# Template.net
KiCad netlist of a schematic drawn in EAGLE
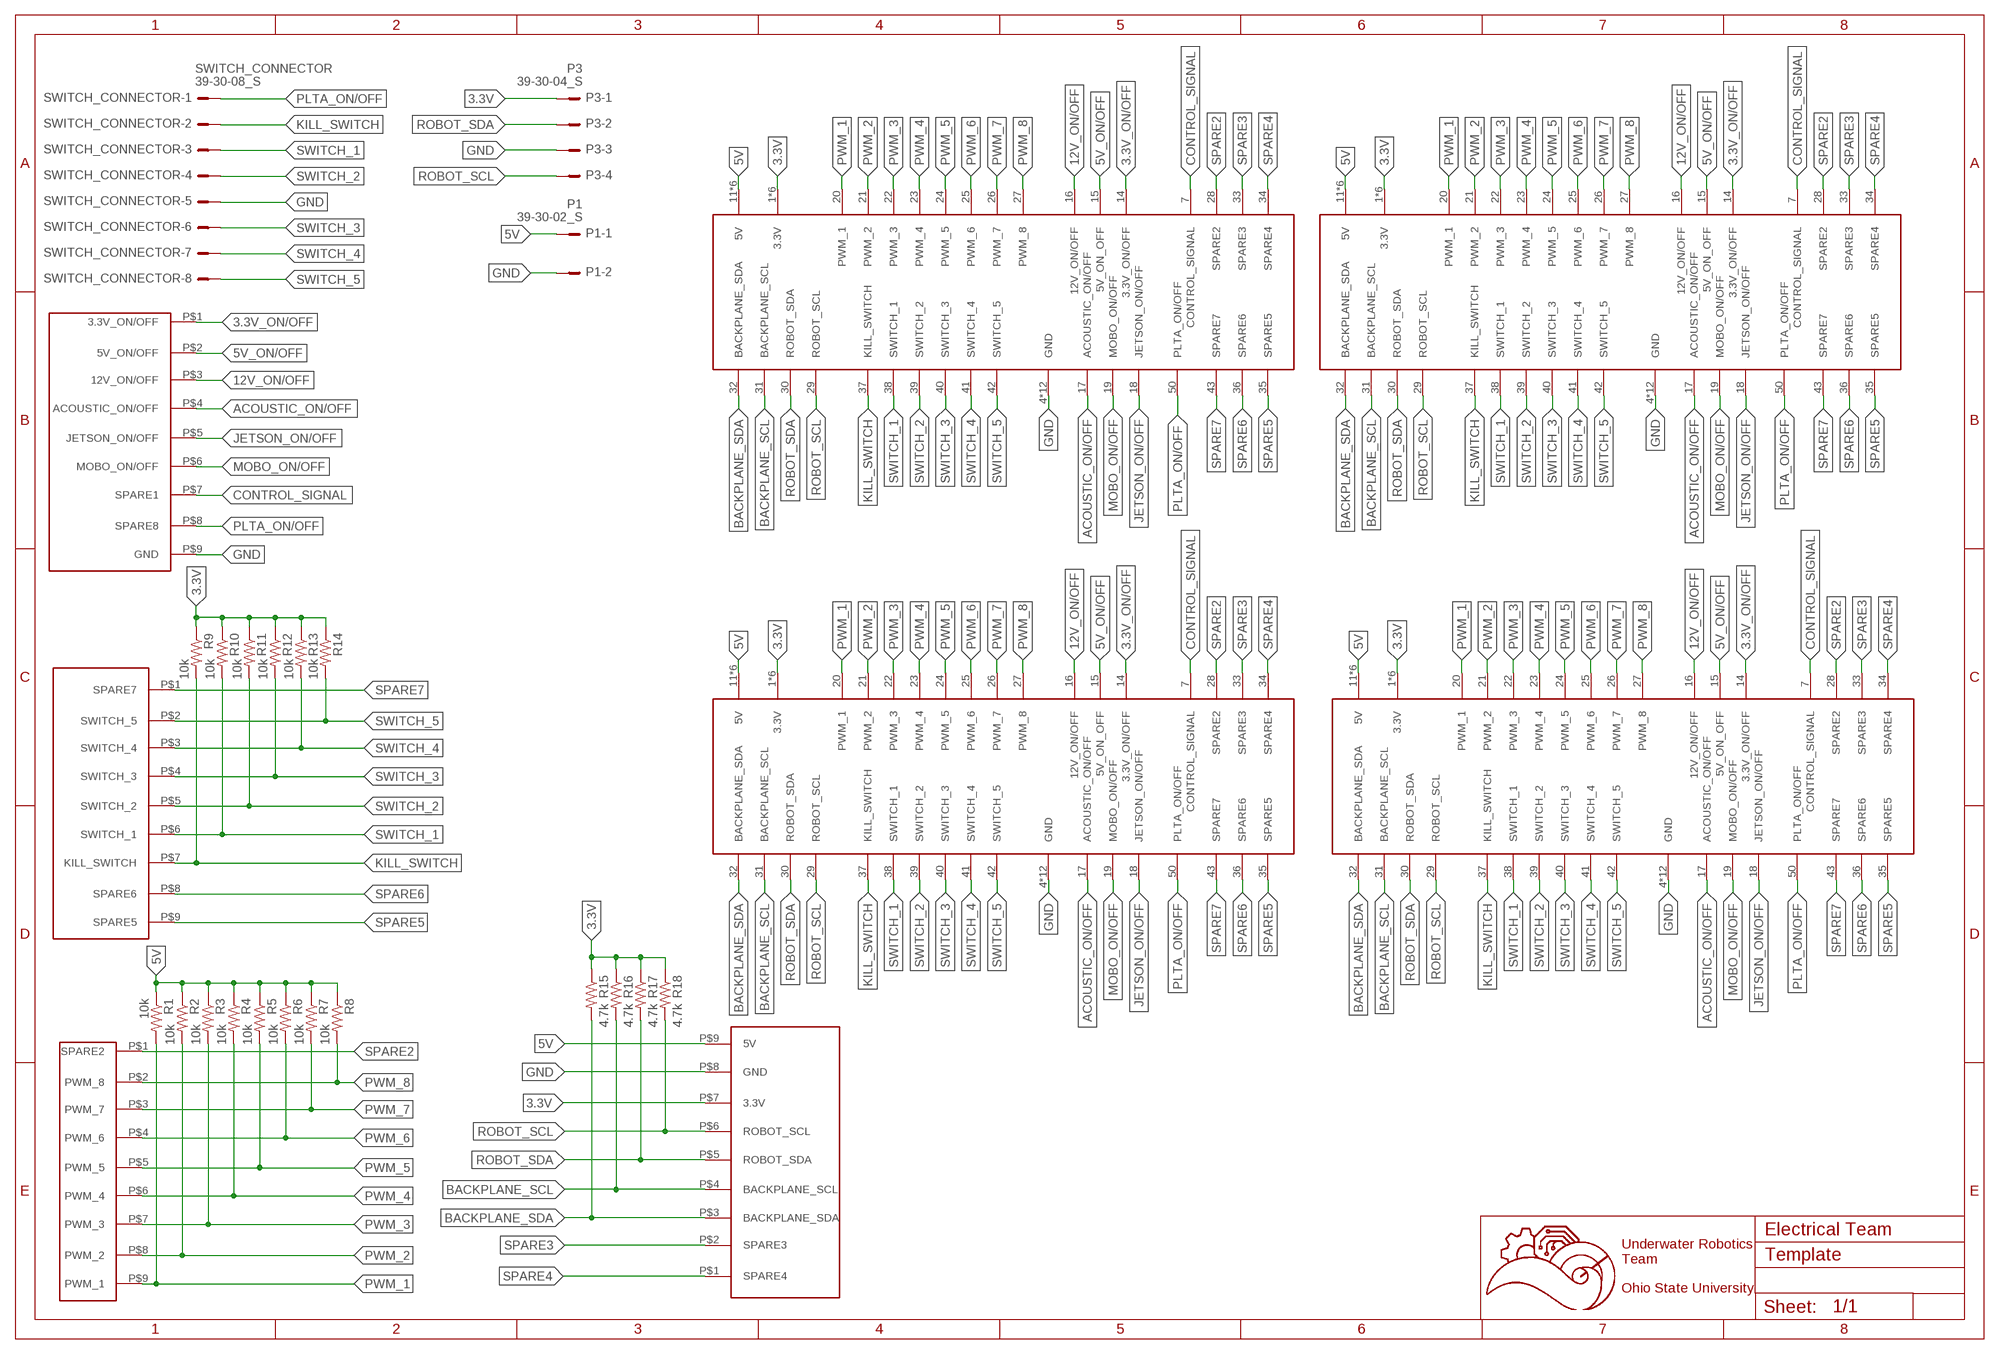
[diagram p0: schematic, sheet 1]

(export (version "E")
  (design (tool "Eeschema 10.0.6"))
  (components
    (comp (ref "P1")
      (value "39-30-02_S")
      (footprint "eagle-import:39-30-_02_")
      (libsource (lib "eagle-import") (part "39-30-?02?_S"))
    )
    (comp (ref "P3")
      (value "39-30-04_S")
      (footprint "eagle-import:39-30-_04_")
      (libsource (lib "eagle-import") (part "39-30-?04?_S"))
    )
    (comp (ref "R1")
      (value "10k")
      (footprint "eagle-import:R0603")
      (libsource (lib "eagle-import") (part "R-US_R0603"))
    )
    (comp (ref "R2")
      (value "10k")
      (footprint "eagle-import:R0603")
      (libsource (lib "eagle-import") (part "R-US_R0603"))
    )
    (comp (ref "R3")
      (value "10k")
      (footprint "eagle-import:R0603")
      (libsource (lib "eagle-import") (part "R-US_R0603"))
    )
    (comp (ref "R4")
      (value "10k")
      (footprint "eagle-import:R0603")
      (libsource (lib "eagle-import") (part "R-US_R0603"))
    )
    (comp (ref "R5")
      (value "10k")
      (footprint "eagle-import:R0603")
      (libsource (lib "eagle-import") (part "R-US_R0603"))
    )
    (comp (ref "R6")
      (value "10k")
      (footprint "eagle-import:R0603")
      (libsource (lib "eagle-import") (part "R-US_R0603"))
    )
    (comp (ref "R7")
      (value "10k")
      (footprint "eagle-import:R0603")
      (libsource (lib "eagle-import") (part "R-US_R0603"))
    )
    (comp (ref "R8")
      (value "10k")
      (footprint "eagle-import:R0603")
      (libsource (lib "eagle-import") (part "R-US_R0603"))
    )
    (comp (ref "R9")
      (value "10k")
      (footprint "eagle-import:R0603")
      (libsource (lib "eagle-import") (part "R-US_R0603"))
    )
    (comp (ref "R10")
      (value "10k")
      (footprint "eagle-import:R0603")
      (libsource (lib "eagle-import") (part "R-US_R0603"))
    )
    (comp (ref "R11")
      (value "10k")
      (footprint "eagle-import:R0603")
      (libsource (lib "eagle-import") (part "R-US_R0603"))
    )
    (comp (ref "R12")
      (value "10k")
      (footprint "eagle-import:R0603")
      (libsource (lib "eagle-import") (part "R-US_R0603"))
    )
    (comp (ref "R13")
      (value "10k")
      (footprint "eagle-import:R0603")
      (libsource (lib "eagle-import") (part "R-US_R0603"))
    )
    (comp (ref "R14")
      (value "10k")
      (footprint "eagle-import:R0603")
      (libsource (lib "eagle-import") (part "R-US_R0603"))
    )
    (comp (ref "R15")
      (value "4.7k")
      (footprint "eagle-import:R0603")
      (libsource (lib "eagle-import") (part "R-US_R0603"))
    )
    (comp (ref "R16")
      (value "4.7k")
      (footprint "eagle-import:R0603")
      (libsource (lib "eagle-import") (part "R-US_R0603"))
    )
    (comp (ref "R17")
      (value "4.7k")
      (footprint "eagle-import:R0603")
      (libsource (lib "eagle-import") (part "R-US_R0603"))
    )
    (comp (ref "R18")
      (value "4.7k")
      (footprint "eagle-import:R0603")
      (libsource (lib "eagle-import") (part "R-US_R0603"))
    )
    (comp (ref "SWITCH_CONNECTOR")
      (value "39-30-08_S")
      (footprint "eagle-import:39-30-_08_")
      (libsource (lib "eagle-import") (part "39-30-?08?_S"))
    )
    (comp (ref "U$1")
      (value "5530843-FEMALE")
      (footprint "eagle-import:5530843-6-BACKPLANEMATE")
      (libsource (lib "eagle-import") (part "5530843-FEMALE"))
    )
    (comp (ref "U$2")
      (value "5530843-FEMALE")
      (footprint "eagle-import:5530843-6-BACKPLANEMATE")
      (libsource (lib "eagle-import") (part "5530843-FEMALE"))
    )
    (comp (ref "U$3")
      (value "5530843-FEMALE")
      (footprint "eagle-import:5530843-6-BACKPLANEMATE")
      (libsource (lib "eagle-import") (part "5530843-FEMALE"))
    )
    (comp (ref "U$4")
      (value "5530843-FEMALE")
      (footprint "eagle-import:5530843-6-BACKPLANEMATE")
      (libsource (lib "eagle-import") (part "5530843-FEMALE"))
    )
    (comp (ref "U$5")
      (value "929870-01-09_1")
      (footprint "eagle-import:929852-01-09_1ROW")
      (libsource (lib "eagle-import") (part "929870-01-09_1"))
    )
    (comp (ref "U$6")
      (value "929870-01-09_2")
      (footprint "eagle-import:929852-01-09_1ROW")
      (libsource (lib "eagle-import") (part "929870-01-09_2"))
    )
    (comp (ref "U$7")
      (value "929870-01-09_3")
      (footprint "eagle-import:929852-01-09_1ROW")
      (libsource (lib "eagle-import") (part "929870-01-09_3"))
    )
    (comp (ref "U$8")
      (value "929870-01-09_4")
      (footprint "eagle-import:929852-01-09_1ROW")
      (libsource (lib "eagle-import") (part "929870-01-09_4"))
    )
  )
  (nets
    (net (code "1") (name "3.3V") (class "Default")
      (node (ref "P3") (pin "1") (pinfunction "P_1") (pintype "passive"))
      (node (ref "R10") (pin "1") (pinfunction "1_1") (pintype "passive"))
      (node (ref "R11") (pin "1") (pinfunction "1_1") (pintype "passive"))
      (node (ref "R12") (pin "1") (pinfunction "1_1") (pintype "passive"))
      (node (ref "R13") (pin "1") (pinfunction "1_1") (pintype "passive"))
      (node (ref "R14") (pin "1") (pinfunction "1_1") (pintype "passive"))
      (node (ref "R15") (pin "1") (pinfunction "1_1") (pintype "passive"))
      (node (ref "R16") (pin "1") (pinfunction "1_1") (pintype "passive"))
      (node (ref "R17") (pin "1") (pinfunction "1_1") (pintype "passive"))
      (node (ref "R18") (pin "1") (pinfunction "1_1") (pintype "passive"))
      (node (ref "R9") (pin "1") (pinfunction "1_1") (pintype "passive"))
      (node (ref "U$1") (pin "1") (pinfunction "3.3V_1") (pintype "bidirectional"))
      (node (ref "U$1") (pin "2") (pinfunction "3.3V_2") (pintype "bidirectional"))
      (node (ref "U$1") (pin "3") (pinfunction "3.3V_3") (pintype "bidirectional"))
      (node (ref "U$1") (pin "54") (pinfunction "3.3V_54") (pintype "bidirectional"))
      (node (ref "U$1") (pin "55") (pinfunction "3.3V_55") (pintype "bidirectional"))
      (node (ref "U$1") (pin "56") (pinfunction "3.3V_56") (pintype "bidirectional"))
      (node (ref "U$2") (pin "1") (pinfunction "3.3V_1") (pintype "bidirectional"))
      (node (ref "U$2") (pin "2") (pinfunction "3.3V_2") (pintype "bidirectional"))
      (node (ref "U$2") (pin "3") (pinfunction "3.3V_3") (pintype "bidirectional"))
      (node (ref "U$2") (pin "54") (pinfunction "3.3V_54") (pintype "bidirectional"))
      (node (ref "U$2") (pin "55") (pinfunction "3.3V_55") (pintype "bidirectional"))
      (node (ref "U$2") (pin "56") (pinfunction "3.3V_56") (pintype "bidirectional"))
      (node (ref "U$3") (pin "1") (pinfunction "3.3V_1") (pintype "bidirectional"))
      (node (ref "U$3") (pin "2") (pinfunction "3.3V_2") (pintype "bidirectional"))
      (node (ref "U$3") (pin "3") (pinfunction "3.3V_3") (pintype "bidirectional"))
      (node (ref "U$3") (pin "54") (pinfunction "3.3V_54") (pintype "bidirectional"))
      (node (ref "U$3") (pin "55") (pinfunction "3.3V_55") (pintype "bidirectional"))
      (node (ref "U$3") (pin "56") (pinfunction "3.3V_56") (pintype "bidirectional"))
      (node (ref "U$4") (pin "1") (pinfunction "3.3V_1") (pintype "bidirectional"))
      (node (ref "U$4") (pin "2") (pinfunction "3.3V_2") (pintype "bidirectional"))
      (node (ref "U$4") (pin "3") (pinfunction "3.3V_3") (pintype "bidirectional"))
      (node (ref "U$4") (pin "54") (pinfunction "3.3V_54") (pintype "bidirectional"))
      (node (ref "U$4") (pin "55") (pinfunction "3.3V_55") (pintype "bidirectional"))
      (node (ref "U$4") (pin "56") (pinfunction "3.3V_56") (pintype "bidirectional"))
      (node (ref "U$8") (pin "P$7") (pinfunction "3.3V_P$7") (pintype "bidirectional"))
    )
    (net (code "2") (name "3.3V_ON{slash}OFF") (class "Default")
      (node (ref "U$1") (pin "14") (pinfunction "3.3V_ON/OFF_14") (pintype "bidirectional"))
      (node (ref "U$2") (pin "14") (pinfunction "3.3V_ON/OFF_14") (pintype "bidirectional"))
      (node (ref "U$3") (pin "14") (pinfunction "3.3V_ON/OFF_14") (pintype "bidirectional"))
      (node (ref "U$4") (pin "14") (pinfunction "3.3V_ON/OFF_14") (pintype "bidirectional"))
      (node (ref "U$7") (pin "P$1") (pinfunction "3.3V_ON/OFF_P$1") (pintype "bidirectional"))
    )
    (net (code "3") (name "5V") (class "Default")
      (node (ref "P1") (pin "1") (pinfunction "P_1") (pintype "passive"))
      (node (ref "R1") (pin "1") (pinfunction "1_1") (pintype "passive"))
      (node (ref "R2") (pin "1") (pinfunction "1_1") (pintype "passive"))
      (node (ref "R3") (pin "1") (pinfunction "1_1") (pintype "passive"))
      (node (ref "R4") (pin "1") (pinfunction "1_1") (pintype "passive"))
      (node (ref "R5") (pin "1") (pinfunction "1_1") (pintype "passive"))
      (node (ref "R6") (pin "1") (pinfunction "1_1") (pintype "passive"))
      (node (ref "R7") (pin "1") (pinfunction "1_1") (pintype "passive"))
      (node (ref "R8") (pin "1") (pinfunction "1_1") (pintype "passive"))
      (node (ref "U$1") (pin "11") (pinfunction "5V_11") (pintype "bidirectional"))
      (node (ref "U$1") (pin "12") (pinfunction "5V_12") (pintype "bidirectional"))
      (node (ref "U$1") (pin "13") (pinfunction "5V_13") (pintype "bidirectional"))
      (node (ref "U$1") (pin "44") (pinfunction "5V_44") (pintype "bidirectional"))
      (node (ref "U$1") (pin "45") (pinfunction "5V_45") (pintype "bidirectional"))
      (node (ref "U$1") (pin "46") (pinfunction "5V_46") (pintype "bidirectional"))
      (node (ref "U$2") (pin "11") (pinfunction "5V_11") (pintype "bidirectional"))
      (node (ref "U$2") (pin "12") (pinfunction "5V_12") (pintype "bidirectional"))
      (node (ref "U$2") (pin "13") (pinfunction "5V_13") (pintype "bidirectional"))
      (node (ref "U$2") (pin "44") (pinfunction "5V_44") (pintype "bidirectional"))
      (node (ref "U$2") (pin "45") (pinfunction "5V_45") (pintype "bidirectional"))
      (node (ref "U$2") (pin "46") (pinfunction "5V_46") (pintype "bidirectional"))
      (node (ref "U$3") (pin "11") (pinfunction "5V_11") (pintype "bidirectional"))
      (node (ref "U$3") (pin "12") (pinfunction "5V_12") (pintype "bidirectional"))
      (node (ref "U$3") (pin "13") (pinfunction "5V_13") (pintype "bidirectional"))
      (node (ref "U$3") (pin "44") (pinfunction "5V_44") (pintype "bidirectional"))
      (node (ref "U$3") (pin "45") (pinfunction "5V_45") (pintype "bidirectional"))
      (node (ref "U$3") (pin "46") (pinfunction "5V_46") (pintype "bidirectional"))
      (node (ref "U$4") (pin "11") (pinfunction "5V_11") (pintype "bidirectional"))
      (node (ref "U$4") (pin "12") (pinfunction "5V_12") (pintype "bidirectional"))
      (node (ref "U$4") (pin "13") (pinfunction "5V_13") (pintype "bidirectional"))
      (node (ref "U$4") (pin "44") (pinfunction "5V_44") (pintype "bidirectional"))
      (node (ref "U$4") (pin "45") (pinfunction "5V_45") (pintype "bidirectional"))
      (node (ref "U$4") (pin "46") (pinfunction "5V_46") (pintype "bidirectional"))
      (node (ref "U$8") (pin "P$9") (pinfunction "5V_P$9") (pintype "bidirectional"))
    )
    (net (code "4") (name "5V_ON{slash}OFF") (class "Default")
      (node (ref "U$1") (pin "15") (pinfunction "5V_ON_OFF_15") (pintype "bidirectional"))
      (node (ref "U$2") (pin "15") (pinfunction "5V_ON_OFF_15") (pintype "bidirectional"))
      (node (ref "U$3") (pin "15") (pinfunction "5V_ON_OFF_15") (pintype "bidirectional"))
      (node (ref "U$4") (pin "15") (pinfunction "5V_ON_OFF_15") (pintype "bidirectional"))
      (node (ref "U$7") (pin "P$2") (pinfunction "5V_ON/OFF_P$2") (pintype "bidirectional"))
    )
    (net (code "5") (name "12V_ON{slash}OFF") (class "Default")
      (node (ref "U$1") (pin "16") (pinfunction "12V_ON/OFF_16") (pintype "bidirectional"))
      (node (ref "U$2") (pin "16") (pinfunction "12V_ON/OFF_16") (pintype "bidirectional"))
      (node (ref "U$3") (pin "16") (pinfunction "12V_ON/OFF_16") (pintype "bidirectional"))
      (node (ref "U$4") (pin "16") (pinfunction "12V_ON/OFF_16") (pintype "bidirectional"))
      (node (ref "U$7") (pin "P$3") (pinfunction "12V_ON/OFF_P$3") (pintype "bidirectional"))
    )
    (net (code "6") (name "ACOUSTIC_ON{slash}OFF") (class "Default")
      (node (ref "U$1") (pin "17") (pinfunction "ACOUSTIC_ON/OFF_17") (pintype "bidirectional"))
      (node (ref "U$2") (pin "17") (pinfunction "ACOUSTIC_ON/OFF_17") (pintype "bidirectional"))
      (node (ref "U$3") (pin "17") (pinfunction "ACOUSTIC_ON/OFF_17") (pintype "bidirectional"))
      (node (ref "U$4") (pin "17") (pinfunction "ACOUSTIC_ON/OFF_17") (pintype "bidirectional"))
      (node (ref "U$7") (pin "P$4") (pinfunction "ACOUSTIC_ON/OFF_P$4") (pintype "bidirectional"))
    )
    (net (code "7") (name "BACKPLANE_SCL") (class "Default")
      (node (ref "R16") (pin "2") (pinfunction "2_2") (pintype "passive"))
      (node (ref "U$1") (pin "31") (pinfunction "BACKPLANE_SCL_31") (pintype "bidirectional"))
      (node (ref "U$2") (pin "31") (pinfunction "BACKPLANE_SCL_31") (pintype "bidirectional"))
      (node (ref "U$3") (pin "31") (pinfunction "BACKPLANE_SCL_31") (pintype "bidirectional"))
      (node (ref "U$4") (pin "31") (pinfunction "BACKPLANE_SCL_31") (pintype "bidirectional"))
      (node (ref "U$8") (pin "P$4") (pinfunction "BACKPLANE_SCL_P$4") (pintype "bidirectional"))
    )
    (net (code "8") (name "BACKPLANE_SDA") (class "Default")
      (node (ref "R15") (pin "2") (pinfunction "2_2") (pintype "passive"))
      (node (ref "U$1") (pin "32") (pinfunction "BACKPLANE_SDA_32") (pintype "bidirectional"))
      (node (ref "U$2") (pin "32") (pinfunction "BACKPLANE_SDA_32") (pintype "bidirectional"))
      (node (ref "U$3") (pin "32") (pinfunction "BACKPLANE_SDA_32") (pintype "bidirectional"))
      (node (ref "U$4") (pin "32") (pinfunction "BACKPLANE_SDA_32") (pintype "bidirectional"))
      (node (ref "U$8") (pin "P$3") (pinfunction "BACKPLANE_SDA_P$3") (pintype "bidirectional"))
    )
    (net (code "9") (name "CONTROL_SIGNAL") (class "Default")
      (node (ref "U$1") (pin "7") (pinfunction "CONTROL_SIGNAL_7") (pintype "bidirectional"))
      (node (ref "U$2") (pin "7") (pinfunction "CONTROL_SIGNAL_7") (pintype "bidirectional"))
      (node (ref "U$3") (pin "7") (pinfunction "CONTROL_SIGNAL_7") (pintype "bidirectional"))
      (node (ref "U$4") (pin "7") (pinfunction "CONTROL_SIGNAL_7") (pintype "bidirectional"))
      (node (ref "U$7") (pin "P$7") (pinfunction "SPARE1_P$7") (pintype "bidirectional"))
    )
    (net (code "10") (name "GND") (class "Default")
      (node (ref "P1") (pin "2") (pinfunction "P_2") (pintype "passive"))
      (node (ref "P3") (pin "3") (pinfunction "P_3") (pintype "passive"))
      (node (ref "SWITCH_CONNECTOR") (pin "5") (pinfunction "P_5") (pintype "passive"))
      (node (ref "U$1") (pin "10") (pinfunction "GND_10") (pintype "bidirectional"))
      (node (ref "U$1") (pin "4") (pinfunction "GND_4") (pintype "bidirectional"))
      (node (ref "U$1") (pin "47") (pinfunction "GND_47") (pintype "bidirectional"))
      (node (ref "U$1") (pin "48") (pinfunction "GND_48") (pintype "bidirectional"))
      (node (ref "U$1") (pin "49") (pinfunction "GND_49") (pintype "bidirectional"))
      (node (ref "U$1") (pin "5") (pinfunction "GND_5") (pintype "bidirectional"))
      (node (ref "U$1") (pin "51") (pinfunction "GND_51") (pintype "bidirectional"))
      (node (ref "U$1") (pin "52") (pinfunction "GND_52") (pintype "bidirectional"))
      (node (ref "U$1") (pin "53") (pinfunction "GND_53") (pintype "bidirectional"))
      (node (ref "U$1") (pin "6") (pinfunction "GND_6") (pintype "bidirectional"))
      (node (ref "U$1") (pin "8") (pinfunction "GND_8") (pintype "bidirectional"))
      (node (ref "U$1") (pin "9") (pinfunction "GND_9") (pintype "bidirectional"))
      (node (ref "U$2") (pin "10") (pinfunction "GND_10") (pintype "bidirectional"))
      (node (ref "U$2") (pin "4") (pinfunction "GND_4") (pintype "bidirectional"))
      (node (ref "U$2") (pin "47") (pinfunction "GND_47") (pintype "bidirectional"))
      (node (ref "U$2") (pin "48") (pinfunction "GND_48") (pintype "bidirectional"))
      (node (ref "U$2") (pin "49") (pinfunction "GND_49") (pintype "bidirectional"))
      (node (ref "U$2") (pin "5") (pinfunction "GND_5") (pintype "bidirectional"))
      (node (ref "U$2") (pin "51") (pinfunction "GND_51") (pintype "bidirectional"))
      (node (ref "U$2") (pin "52") (pinfunction "GND_52") (pintype "bidirectional"))
      (node (ref "U$2") (pin "53") (pinfunction "GND_53") (pintype "bidirectional"))
      (node (ref "U$2") (pin "6") (pinfunction "GND_6") (pintype "bidirectional"))
      (node (ref "U$2") (pin "8") (pinfunction "GND_8") (pintype "bidirectional"))
      (node (ref "U$2") (pin "9") (pinfunction "GND_9") (pintype "bidirectional"))
      (node (ref "U$3") (pin "10") (pinfunction "GND_10") (pintype "bidirectional"))
      (node (ref "U$3") (pin "4") (pinfunction "GND_4") (pintype "bidirectional"))
      (node (ref "U$3") (pin "47") (pinfunction "GND_47") (pintype "bidirectional"))
      (node (ref "U$3") (pin "48") (pinfunction "GND_48") (pintype "bidirectional"))
      (node (ref "U$3") (pin "49") (pinfunction "GND_49") (pintype "bidirectional"))
      (node (ref "U$3") (pin "5") (pinfunction "GND_5") (pintype "bidirectional"))
      (node (ref "U$3") (pin "51") (pinfunction "GND_51") (pintype "bidirectional"))
      (node (ref "U$3") (pin "52") (pinfunction "GND_52") (pintype "bidirectional"))
      (node (ref "U$3") (pin "53") (pinfunction "GND_53") (pintype "bidirectional"))
      (node (ref "U$3") (pin "6") (pinfunction "GND_6") (pintype "bidirectional"))
      (node (ref "U$3") (pin "8") (pinfunction "GND_8") (pintype "bidirectional"))
      (node (ref "U$3") (pin "9") (pinfunction "GND_9") (pintype "bidirectional"))
      (node (ref "U$4") (pin "10") (pinfunction "GND_10") (pintype "bidirectional"))
      (node (ref "U$4") (pin "4") (pinfunction "GND_4") (pintype "bidirectional"))
      (node (ref "U$4") (pin "47") (pinfunction "GND_47") (pintype "bidirectional"))
      (node (ref "U$4") (pin "48") (pinfunction "GND_48") (pintype "bidirectional"))
      (node (ref "U$4") (pin "49") (pinfunction "GND_49") (pintype "bidirectional"))
      (node (ref "U$4") (pin "5") (pinfunction "GND_5") (pintype "bidirectional"))
      (node (ref "U$4") (pin "51") (pinfunction "GND_51") (pintype "bidirectional"))
      (node (ref "U$4") (pin "52") (pinfunction "GND_52") (pintype "bidirectional"))
      (node (ref "U$4") (pin "53") (pinfunction "GND_53") (pintype "bidirectional"))
      (node (ref "U$4") (pin "6") (pinfunction "GND_6") (pintype "bidirectional"))
      (node (ref "U$4") (pin "8") (pinfunction "GND_8") (pintype "bidirectional"))
      (node (ref "U$4") (pin "9") (pinfunction "GND_9") (pintype "bidirectional"))
      (node (ref "U$7") (pin "P$9") (pinfunction "GND_P$9") (pintype "bidirectional"))
      (node (ref "U$8") (pin "P$8") (pinfunction "GND_P$8") (pintype "bidirectional"))
    )
    (net (code "11") (name "JETSON_ON{slash}OFF") (class "Default")
      (node (ref "U$1") (pin "18") (pinfunction "JETSON_ON/OFF_18") (pintype "bidirectional"))
      (node (ref "U$2") (pin "18") (pinfunction "JETSON_ON/OFF_18") (pintype "bidirectional"))
      (node (ref "U$3") (pin "18") (pinfunction "JETSON_ON/OFF_18") (pintype "bidirectional"))
      (node (ref "U$4") (pin "18") (pinfunction "JETSON_ON/OFF_18") (pintype "bidirectional"))
      (node (ref "U$7") (pin "P$5") (pinfunction "JETSON_ON/OFF_P$5") (pintype "bidirectional"))
    )
    (net (code "12") (name "KILL_SWITCH") (class "Default")
      (node (ref "R9") (pin "2") (pinfunction "2_2") (pintype "passive"))
      (node (ref "SWITCH_CONNECTOR") (pin "2") (pinfunction "P_2") (pintype "passive"))
      (node (ref "U$1") (pin "37") (pinfunction "KILL_SWITCH_37") (pintype "output"))
      (node (ref "U$2") (pin "37") (pinfunction "KILL_SWITCH_37") (pintype "output"))
      (node (ref "U$3") (pin "37") (pinfunction "KILL_SWITCH_37") (pintype "output"))
      (node (ref "U$4") (pin "37") (pinfunction "KILL_SWITCH_37") (pintype "output"))
      (node (ref "U$5") (pin "P$7") (pinfunction "KILL_SWITCH_P$7") (pintype "bidirectional"))
    )
    (net (code "13") (name "MOBO_ON{slash}OFF") (class "Default")
      (node (ref "U$1") (pin "19") (pinfunction "MOBO_ON/OFF_19") (pintype "bidirectional"))
      (node (ref "U$2") (pin "19") (pinfunction "MOBO_ON/OFF_19") (pintype "bidirectional"))
      (node (ref "U$3") (pin "19") (pinfunction "MOBO_ON/OFF_19") (pintype "bidirectional"))
      (node (ref "U$4") (pin "19") (pinfunction "MOBO_ON/OFF_19") (pintype "bidirectional"))
      (node (ref "U$7") (pin "P$6") (pinfunction "MOBO_ON/OFF_P$6") (pintype "bidirectional"))
    )
    (net (code "14") (name "PLTA_ON{slash}OFF") (class "Default")
      (node (ref "SWITCH_CONNECTOR") (pin "1") (pinfunction "P_1") (pintype "passive"))
      (node (ref "U$1") (pin "50") (pinfunction "PLTA_ON/OFF_50") (pintype "bidirectional"))
      (node (ref "U$2") (pin "50") (pinfunction "PLTA_ON/OFF_50") (pintype "bidirectional"))
      (node (ref "U$3") (pin "50") (pinfunction "PLTA_ON/OFF_50") (pintype "bidirectional"))
      (node (ref "U$4") (pin "50") (pinfunction "PLTA_ON/OFF_50") (pintype "bidirectional"))
      (node (ref "U$7") (pin "P$8") (pinfunction "SPARE8_P$8") (pintype "bidirectional"))
    )
    (net (code "15") (name "PWM_1") (class "Default")
      (node (ref "R1") (pin "2") (pinfunction "2_2") (pintype "passive"))
      (node (ref "U$1") (pin "20") (pinfunction "PWM_1_20") (pintype "bidirectional"))
      (node (ref "U$2") (pin "20") (pinfunction "PWM_1_20") (pintype "bidirectional"))
      (node (ref "U$3") (pin "20") (pinfunction "PWM_1_20") (pintype "bidirectional"))
      (node (ref "U$4") (pin "20") (pinfunction "PWM_1_20") (pintype "bidirectional"))
      (node (ref "U$6") (pin "P$9") (pinfunction "PWM_1_P$9") (pintype "bidirectional"))
    )
    (net (code "16") (name "PWM_2") (class "Default")
      (node (ref "R2") (pin "2") (pinfunction "2_2") (pintype "passive"))
      (node (ref "U$1") (pin "21") (pinfunction "PWM_2_21") (pintype "bidirectional"))
      (node (ref "U$2") (pin "21") (pinfunction "PWM_2_21") (pintype "bidirectional"))
      (node (ref "U$3") (pin "21") (pinfunction "PWM_2_21") (pintype "bidirectional"))
      (node (ref "U$4") (pin "21") (pinfunction "PWM_2_21") (pintype "bidirectional"))
      (node (ref "U$6") (pin "P$8") (pinfunction "PWM_2_P$8") (pintype "bidirectional"))
    )
    (net (code "17") (name "PWM_3") (class "Default")
      (node (ref "R3") (pin "2") (pinfunction "2_2") (pintype "passive"))
      (node (ref "U$1") (pin "22") (pinfunction "PWM_3_22") (pintype "bidirectional"))
      (node (ref "U$2") (pin "22") (pinfunction "PWM_3_22") (pintype "bidirectional"))
      (node (ref "U$3") (pin "22") (pinfunction "PWM_3_22") (pintype "bidirectional"))
      (node (ref "U$4") (pin "22") (pinfunction "PWM_3_22") (pintype "bidirectional"))
      (node (ref "U$6") (pin "P$7") (pinfunction "PWM_3_P$7") (pintype "bidirectional"))
    )
    (net (code "18") (name "PWM_4") (class "Default")
      (node (ref "R4") (pin "2") (pinfunction "2_2") (pintype "passive"))
      (node (ref "U$1") (pin "23") (pinfunction "PWM_4_23") (pintype "bidirectional"))
      (node (ref "U$2") (pin "23") (pinfunction "PWM_4_23") (pintype "bidirectional"))
      (node (ref "U$3") (pin "23") (pinfunction "PWM_4_23") (pintype "bidirectional"))
      (node (ref "U$4") (pin "23") (pinfunction "PWM_4_23") (pintype "bidirectional"))
      (node (ref "U$6") (pin "P$6") (pinfunction "PWM_4_P$6") (pintype "bidirectional"))
    )
    (net (code "19") (name "PWM_5") (class "Default")
      (node (ref "R5") (pin "2") (pinfunction "2_2") (pintype "passive"))
      (node (ref "U$1") (pin "24") (pinfunction "PWM_5_24") (pintype "bidirectional"))
      (node (ref "U$2") (pin "24") (pinfunction "PWM_5_24") (pintype "bidirectional"))
      (node (ref "U$3") (pin "24") (pinfunction "PWM_5_24") (pintype "bidirectional"))
      (node (ref "U$4") (pin "24") (pinfunction "PWM_5_24") (pintype "bidirectional"))
      (node (ref "U$6") (pin "P$5") (pinfunction "PWM_5_P$5") (pintype "bidirectional"))
    )
    (net (code "20") (name "PWM_6") (class "Default")
      (node (ref "R6") (pin "2") (pinfunction "2_2") (pintype "passive"))
      (node (ref "U$1") (pin "25") (pinfunction "PWM_6_25") (pintype "bidirectional"))
      (node (ref "U$2") (pin "25") (pinfunction "PWM_6_25") (pintype "bidirectional"))
      (node (ref "U$3") (pin "25") (pinfunction "PWM_6_25") (pintype "bidirectional"))
      (node (ref "U$4") (pin "25") (pinfunction "PWM_6_25") (pintype "bidirectional"))
      (node (ref "U$6") (pin "P$4") (pinfunction "PWM_6_P$4") (pintype "bidirectional"))
    )
    (net (code "21") (name "PWM_7") (class "Default")
      (node (ref "R7") (pin "2") (pinfunction "2_2") (pintype "passive"))
      (node (ref "U$1") (pin "26") (pinfunction "PWM_7_26") (pintype "bidirectional"))
      (node (ref "U$2") (pin "26") (pinfunction "PWM_7_26") (pintype "bidirectional"))
      (node (ref "U$3") (pin "26") (pinfunction "PWM_7_26") (pintype "bidirectional"))
      (node (ref "U$4") (pin "26") (pinfunction "PWM_7_26") (pintype "bidirectional"))
      (node (ref "U$6") (pin "P$3") (pinfunction "PWM_7_P$3") (pintype "bidirectional"))
    )
    (net (code "22") (name "PWM_8") (class "Default")
      (node (ref "R8") (pin "2") (pinfunction "2_2") (pintype "passive"))
      (node (ref "U$1") (pin "27") (pinfunction "PWM_8_27") (pintype "bidirectional"))
      (node (ref "U$2") (pin "27") (pinfunction "PWM_8_27") (pintype "bidirectional"))
      (node (ref "U$3") (pin "27") (pinfunction "PWM_8_27") (pintype "bidirectional"))
      (node (ref "U$4") (pin "27") (pinfunction "PWM_8_27") (pintype "bidirectional"))
      (node (ref "U$6") (pin "P$2") (pinfunction "PWM_8_P$2") (pintype "bidirectional"))
    )
    (net (code "23") (name "ROBOT_SCL") (class "Default")
      (node (ref "P3") (pin "4") (pinfunction "P_4") (pintype "passive"))
      (node (ref "R18") (pin "2") (pinfunction "2_2") (pintype "passive"))
      (node (ref "U$1") (pin "29") (pinfunction "ROBOT_SCL_29") (pintype "bidirectional"))
      (node (ref "U$2") (pin "29") (pinfunction "ROBOT_SCL_29") (pintype "bidirectional"))
      (node (ref "U$3") (pin "29") (pinfunction "ROBOT_SCL_29") (pintype "bidirectional"))
      (node (ref "U$4") (pin "29") (pinfunction "ROBOT_SCL_29") (pintype "bidirectional"))
      (node (ref "U$8") (pin "P$6") (pinfunction "ROBOT_SCL_P$6") (pintype "bidirectional"))
    )
    (net (code "24") (name "ROBOT_SDA") (class "Default")
      (node (ref "P3") (pin "2") (pinfunction "P_2") (pintype "passive"))
      (node (ref "R17") (pin "2") (pinfunction "2_2") (pintype "passive"))
      (node (ref "U$1") (pin "30") (pinfunction "ROBOT_SDA_30") (pintype "bidirectional"))
      (node (ref "U$2") (pin "30") (pinfunction "ROBOT_SDA_30") (pintype "bidirectional"))
      (node (ref "U$3") (pin "30") (pinfunction "ROBOT_SDA_30") (pintype "bidirectional"))
      (node (ref "U$4") (pin "30") (pinfunction "ROBOT_SDA_30") (pintype "bidirectional"))
      (node (ref "U$8") (pin "P$5") (pinfunction "ROBOT_SDA_P$5") (pintype "bidirectional"))
    )
    (net (code "25") (name "SPARE2") (class "Default")
      (node (ref "U$1") (pin "28") (pinfunction "SPARE2_28") (pintype "bidirectional"))
      (node (ref "U$2") (pin "28") (pinfunction "SPARE2_28") (pintype "bidirectional"))
      (node (ref "U$3") (pin "28") (pinfunction "SPARE2_28") (pintype "bidirectional"))
      (node (ref "U$4") (pin "28") (pinfunction "SPARE2_28") (pintype "bidirectional"))
      (node (ref "U$6") (pin "P$1") (pinfunction "SPARE2_P$1") (pintype "bidirectional"))
    )
    (net (code "26") (name "SPARE3") (class "Default")
      (node (ref "U$1") (pin "33") (pinfunction "SPARE3_33") (pintype "bidirectional"))
      (node (ref "U$2") (pin "33") (pinfunction "SPARE3_33") (pintype "bidirectional"))
      (node (ref "U$3") (pin "33") (pinfunction "SPARE3_33") (pintype "bidirectional"))
      (node (ref "U$4") (pin "33") (pinfunction "SPARE3_33") (pintype "bidirectional"))
      (node (ref "U$8") (pin "P$2") (pinfunction "SPARE3_P$2") (pintype "bidirectional"))
    )
    (net (code "27") (name "SPARE4") (class "Default")
      (node (ref "U$1") (pin "34") (pinfunction "SPARE4_34") (pintype "bidirectional"))
      (node (ref "U$2") (pin "34") (pinfunction "SPARE4_34") (pintype "bidirectional"))
      (node (ref "U$3") (pin "34") (pinfunction "SPARE4_34") (pintype "bidirectional"))
      (node (ref "U$4") (pin "34") (pinfunction "SPARE4_34") (pintype "bidirectional"))
      (node (ref "U$8") (pin "P$1") (pinfunction "SPARE4_P$1") (pintype "bidirectional"))
    )
    (net (code "28") (name "SPARE5") (class "Default")
      (node (ref "U$1") (pin "35") (pinfunction "SPARE5_35") (pintype "bidirectional"))
      (node (ref "U$2") (pin "35") (pinfunction "SPARE5_35") (pintype "bidirectional"))
      (node (ref "U$3") (pin "35") (pinfunction "SPARE5_35") (pintype "bidirectional"))
      (node (ref "U$4") (pin "35") (pinfunction "SPARE5_35") (pintype "bidirectional"))
      (node (ref "U$5") (pin "P$9") (pinfunction "SPARE5_P$9") (pintype "bidirectional"))
    )
    (net (code "29") (name "SPARE6") (class "Default")
      (node (ref "U$1") (pin "36") (pinfunction "SPARE6_36") (pintype "bidirectional"))
      (node (ref "U$2") (pin "36") (pinfunction "SPARE6_36") (pintype "bidirectional"))
      (node (ref "U$3") (pin "36") (pinfunction "SPARE6_36") (pintype "bidirectional"))
      (node (ref "U$4") (pin "36") (pinfunction "SPARE6_36") (pintype "bidirectional"))
      (node (ref "U$5") (pin "P$8") (pinfunction "SPARE6_P$8") (pintype "bidirectional"))
    )
    (net (code "30") (name "SPARE7") (class "Default")
      (node (ref "U$1") (pin "43") (pinfunction "SPARE7_43") (pintype "bidirectional"))
      (node (ref "U$2") (pin "43") (pinfunction "SPARE7_43") (pintype "bidirectional"))
      (node (ref "U$3") (pin "43") (pinfunction "SPARE7_43") (pintype "bidirectional"))
      (node (ref "U$4") (pin "43") (pinfunction "SPARE7_43") (pintype "bidirectional"))
      (node (ref "U$5") (pin "P$1") (pinfunction "SPARE7_P$1") (pintype "bidirectional"))
    )
    (net (code "31") (name "SWITCH_1") (class "Default")
      (node (ref "R10") (pin "2") (pinfunction "2_2") (pintype "passive"))
      (node (ref "SWITCH_CONNECTOR") (pin "3") (pinfunction "P_3") (pintype "passive"))
      (node (ref "U$1") (pin "38") (pinfunction "SWITCH_1_38") (pintype "output"))
      (node (ref "U$2") (pin "38") (pinfunction "SWITCH_1_38") (pintype "output"))
      (node (ref "U$3") (pin "38") (pinfunction "SWITCH_1_38") (pintype "output"))
      (node (ref "U$4") (pin "38") (pinfunction "SWITCH_1_38") (pintype "output"))
      (node (ref "U$5") (pin "P$6") (pinfunction "SWITCH_1_P$6") (pintype "bidirectional"))
    )
    (net (code "32") (name "SWITCH_2") (class "Default")
      (node (ref "R11") (pin "2") (pinfunction "2_2") (pintype "passive"))
      (node (ref "SWITCH_CONNECTOR") (pin "4") (pinfunction "P_4") (pintype "passive"))
      (node (ref "U$1") (pin "39") (pinfunction "SWITCH_2_39") (pintype "output"))
      (node (ref "U$2") (pin "39") (pinfunction "SWITCH_2_39") (pintype "output"))
      (node (ref "U$3") (pin "39") (pinfunction "SWITCH_2_39") (pintype "output"))
      (node (ref "U$4") (pin "39") (pinfunction "SWITCH_2_39") (pintype "output"))
      (node (ref "U$5") (pin "P$5") (pinfunction "SWITCH_2_P$5") (pintype "bidirectional"))
    )
    (net (code "33") (name "SWITCH_3") (class "Default")
      (node (ref "R12") (pin "2") (pinfunction "2_2") (pintype "passive"))
      (node (ref "SWITCH_CONNECTOR") (pin "6") (pinfunction "P_6") (pintype "passive"))
      (node (ref "U$1") (pin "40") (pinfunction "SWITCH_3_40") (pintype "output"))
      (node (ref "U$2") (pin "40") (pinfunction "SWITCH_3_40") (pintype "output"))
      (node (ref "U$3") (pin "40") (pinfunction "SWITCH_3_40") (pintype "output"))
      (node (ref "U$4") (pin "40") (pinfunction "SWITCH_3_40") (pintype "output"))
      (node (ref "U$5") (pin "P$4") (pinfunction "SWITCH_3_P$4") (pintype "bidirectional"))
    )
    (net (code "34") (name "SWITCH_4") (class "Default")
      (node (ref "R13") (pin "2") (pinfunction "2_2") (pintype "passive"))
      (node (ref "SWITCH_CONNECTOR") (pin "7") (pinfunction "P_7") (pintype "passive"))
      (node (ref "U$1") (pin "41") (pinfunction "SWITCH_4_41") (pintype "output"))
      (node (ref "U$2") (pin "41") (pinfunction "SWITCH_4_41") (pintype "output"))
      (node (ref "U$3") (pin "41") (pinfunction "SWITCH_4_41") (pintype "output"))
      (node (ref "U$4") (pin "41") (pinfunction "SWITCH_4_41") (pintype "output"))
      (node (ref "U$5") (pin "P$3") (pinfunction "SWITCH_4_P$3") (pintype "bidirectional"))
    )
    (net (code "35") (name "SWITCH_5") (class "Default")
      (node (ref "R14") (pin "2") (pinfunction "2_2") (pintype "passive"))
      (node (ref "SWITCH_CONNECTOR") (pin "8") (pinfunction "P_8") (pintype "passive"))
      (node (ref "U$1") (pin "42") (pinfunction "SWITCH_5_42") (pintype "output"))
      (node (ref "U$2") (pin "42") (pinfunction "SWITCH_5_42") (pintype "output"))
      (node (ref "U$3") (pin "42") (pinfunction "SWITCH_5_42") (pintype "output"))
      (node (ref "U$4") (pin "42") (pinfunction "SWITCH_5_42") (pintype "output"))
      (node (ref "U$5") (pin "P$2") (pinfunction "SWITCH_5_P$2") (pintype "bidirectional"))
    )
  )
)
